# AltiumSTM32_Schematic.net
KiCad netlist of a schematic drawn in Altium Designer
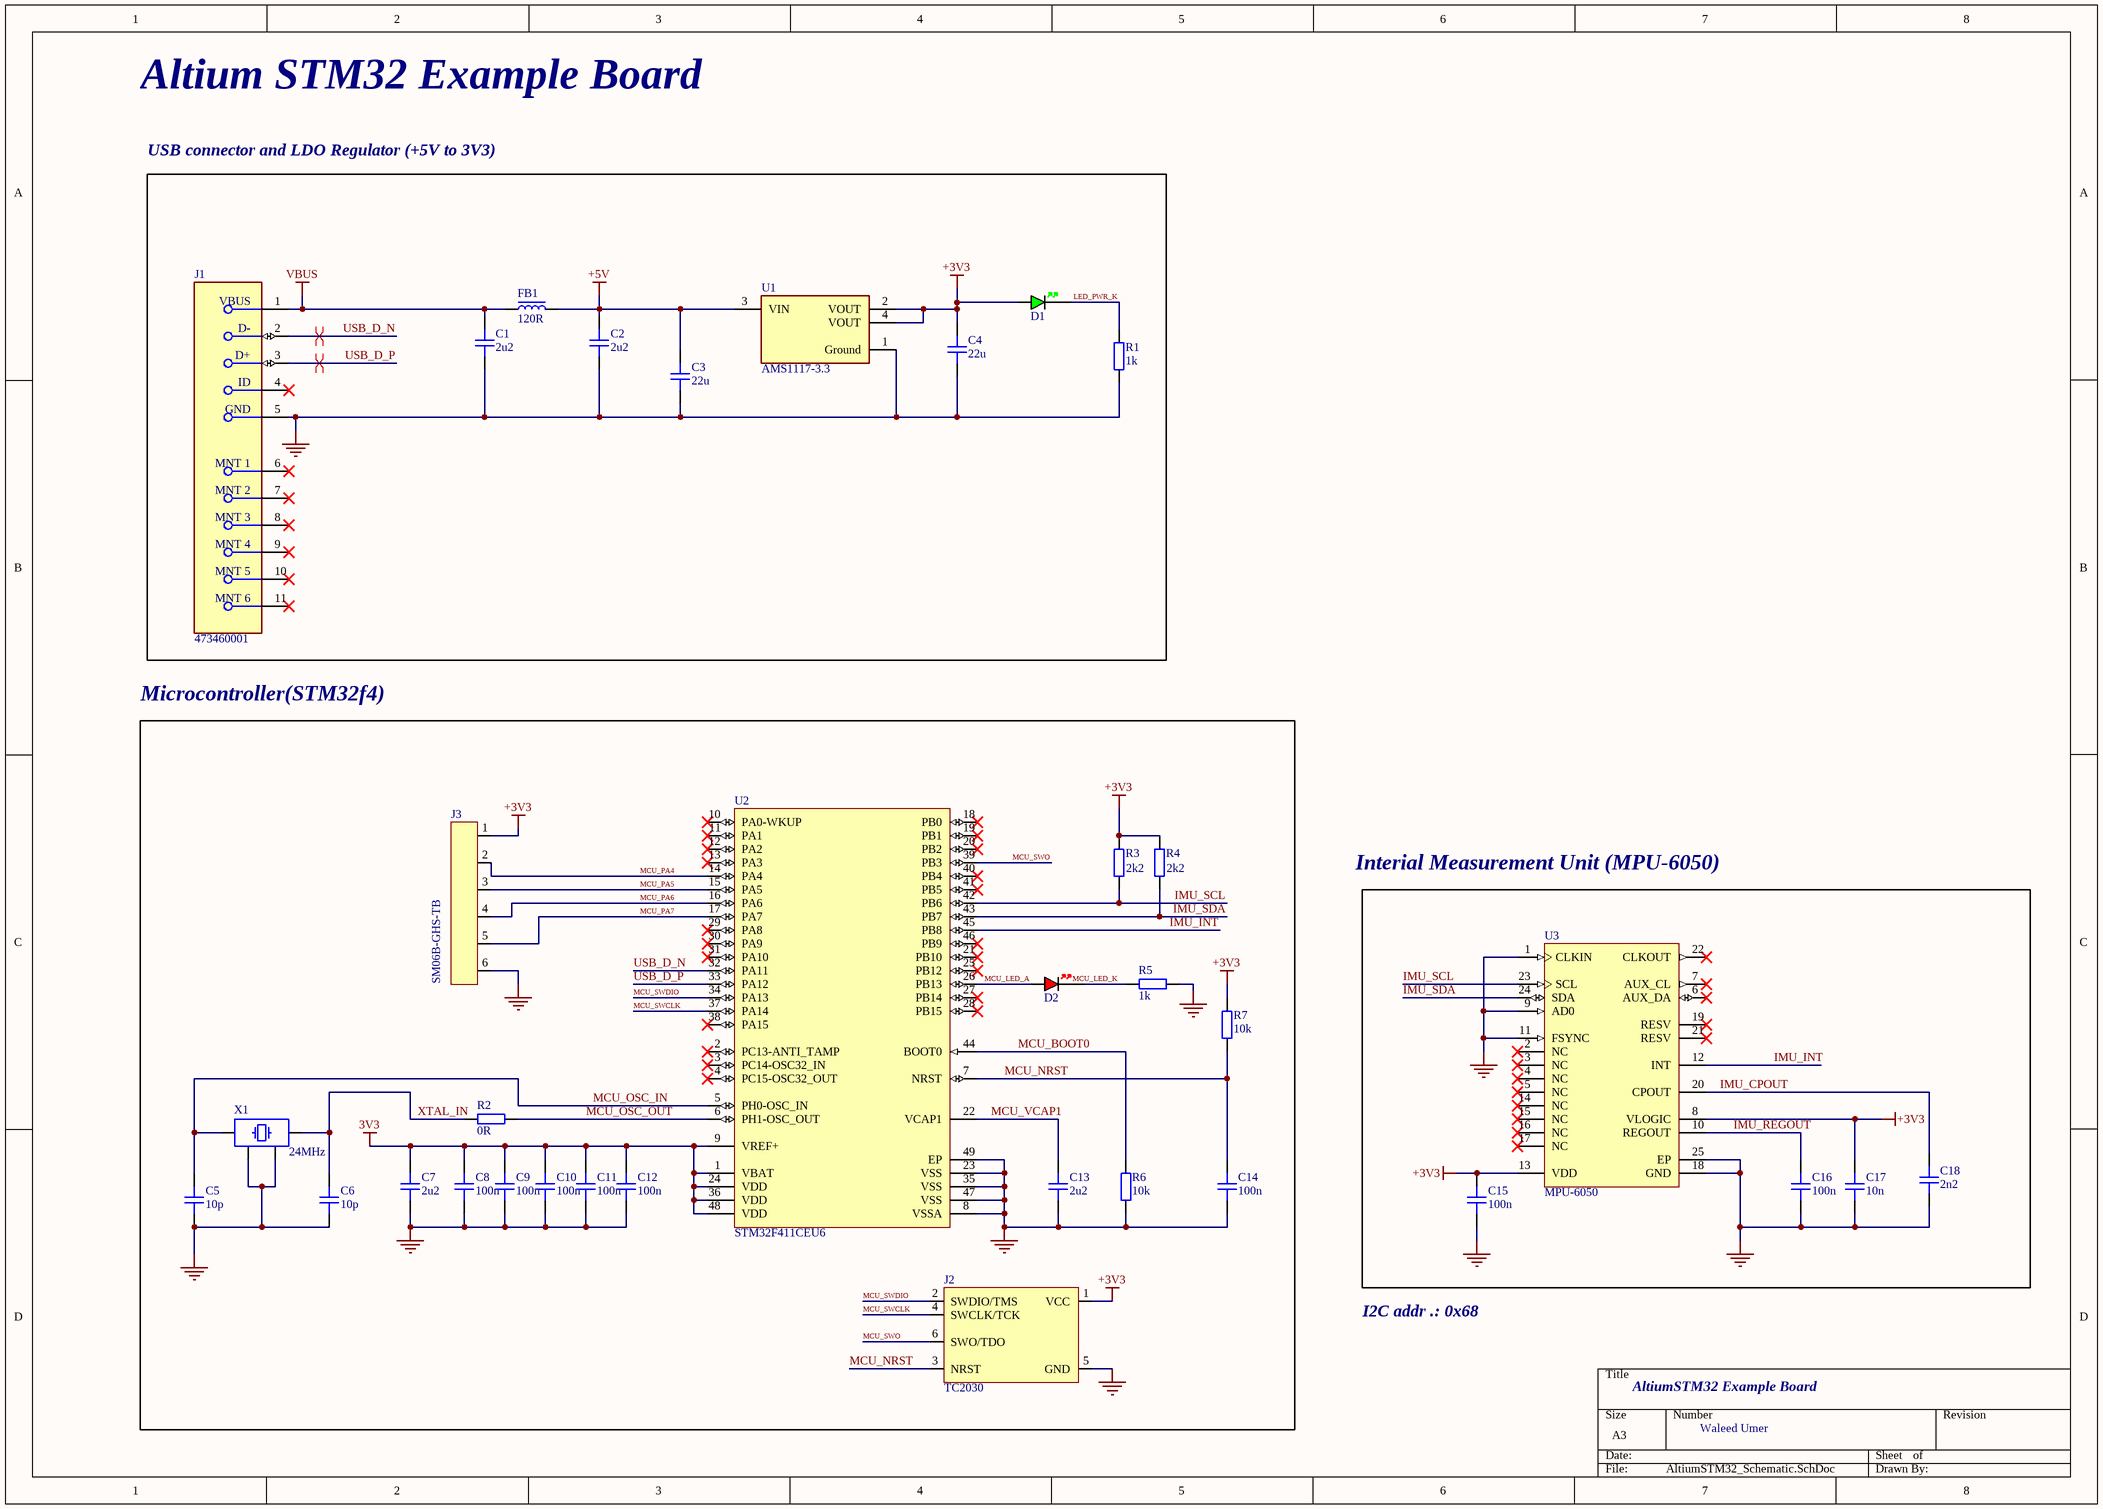
[diagram p0: AltiumSTM32_Schematic.SchDoc]

(export (version "E")
  (design (tool "Eeschema 10.0.6"))
  (components
    (comp (ref "C1")
      (value "2u2")
      (footprint "CAP_0603")
      (description "Capacitor SMD 0603")
      (libsource (lib "Schematic-Lib-PhilsLab") (part "CAP_0603"))
    )
    (comp (ref "C2")
      (value "2u2")
      (footprint "CAP_0603")
      (description "Capacitor SMD 0603")
      (libsource (lib "Schematic-Lib-PhilsLab") (part "CAP_0603"))
    )
    (comp (ref "C3")
      (value "22u")
      (footprint "CAP_0805")
      (description "Capacitor SMD 0805")
      (libsource (lib "Schematic-Lib-PhilsLab") (part "CAP_0805"))
    )
    (comp (ref "C4")
      (value "22u")
      (footprint "CAP_0805")
      (description "Capacitor SMD 0805")
      (libsource (lib "Schematic-Lib-PhilsLab") (part "CAP_0805"))
    )
    (comp (ref "C5")
      (value "10p")
      (footprint "CAP_0402")
      (description "Capacitor SMD 0402")
      (libsource (lib "Schematic-Lib-PhilsLab") (part "CAP_0402"))
    )
    (comp (ref "C6")
      (value "10p")
      (footprint "CAP_0402")
      (description "Capacitor SMD 0402")
      (libsource (lib "Schematic-Lib-PhilsLab") (part "CAP_0402"))
    )
    (comp (ref "C7")
      (value "2u2")
      (footprint "CAP_0603")
      (description "Capacitor SMD 0603")
      (libsource (lib "Schematic-Lib-PhilsLab") (part "CAP_0603"))
    )
    (comp (ref "C8")
      (value "100n")
      (footprint "CAP_0402")
      (description "Capacitor SMD 0402")
      (libsource (lib "Schematic-Lib-PhilsLab") (part "CAP_0402"))
    )
    (comp (ref "C9")
      (value "100n")
      (footprint "CAP_0402")
      (description "Capacitor SMD 0402")
      (libsource (lib "Schematic-Lib-PhilsLab") (part "CAP_0402"))
    )
    (comp (ref "C10")
      (value "100n")
      (footprint "CAP_0402")
      (description "Capacitor SMD 0402")
      (libsource (lib "Schematic-Lib-PhilsLab") (part "CAP_0402"))
    )
    (comp (ref "C11")
      (value "100n")
      (footprint "CAP_0402")
      (description "Capacitor SMD 0402")
      (libsource (lib "Schematic-Lib-PhilsLab") (part "CAP_0402"))
    )
    (comp (ref "C12")
      (value "100n")
      (footprint "CAP_0402")
      (description "Capacitor SMD 0402")
      (libsource (lib "Schematic-Lib-PhilsLab") (part "CAP_0402"))
    )
    (comp (ref "C13")
      (value "2u2")
      (footprint "CAP_0603")
      (description "Capacitor SMD 0603")
      (libsource (lib "Schematic-Lib-PhilsLab") (part "CAP_0603"))
    )
    (comp (ref "C14")
      (value "100n")
      (footprint "CAP_0402")
      (description "Capacitor SMD 0402")
      (libsource (lib "Schematic-Lib-PhilsLab") (part "CAP_0402"))
    )
    (comp (ref "C15")
      (value "100n")
      (footprint "CAP_0402")
      (description "Capacitor SMD 0402")
      (libsource (lib "Schematic-Lib-PhilsLab") (part "CAP_0402"))
    )
    (comp (ref "C16")
      (value "100n")
      (footprint "CAP_0402")
      (description "Capacitor SMD 0402")
      (libsource (lib "Schematic-Lib-PhilsLab") (part "CAP_0402"))
    )
    (comp (ref "C17")
      (value "10n")
      (footprint "CAP_0402")
      (description "Capacitor SMD 0402")
      (libsource (lib "Schematic-Lib-PhilsLab") (part "CAP_0402"))
    )
    (comp (ref "C18")
      (value "2n2")
      (footprint "CAP_0402")
      (description "Capacitor SMD 0402")
      (libsource (lib "Schematic-Lib-PhilsLab") (part "CAP_0402"))
    )
    (comp (ref "D1")
      (value "GREEN")
      (footprint "LED_0402_GREEN")
      (description "LED 0402 GREEN SMD")
      (libsource (lib "Schematic-Lib-PhilsLab") (part "LED_0402_GREEN"))
    )
    (comp (ref "D2")
      (value "RED")
      (footprint "LED_0402_RED")
      (description "LED 0402 RED SMD")
      (libsource (lib "Schematic-Lib-PhilsLab") (part "LED_0402_RED"))
    )
    (comp (ref "FB1")
      (value "120R")
      (footprint "FB_0603")
      (description "Ferrite Bead SMD 0603")
      (libsource (lib "Schematic-Lib-PhilsLab") (part "FB_0603"))
    )
    (comp (ref "J1")
      (value "473460001")
      (footprint "FP-473460001-MFG")
      (description "CONN RCPT USB2.0 MICRO B SMD R/A")
      (fields
        (field (name "OCTOPART") "https://octopart.com/47346-0001-molex-7164928")
        (field (name "MANUFACTURER") "Molex")
      )
      (libsource (lib "Altium Content Vault") (part "53ae1f1d9b557310b43ca686e5bb76a"))
    )
    (comp (ref "J2")
      (value "TC2030")
      (footprint "TC2030-FP")
      (description "Tag-Connect No-Solder SWD Debug Connector DO NOT PLACE")
      (fields (field (name "MANUFACTURER") "Tag-Connect"))
      (libsource (lib "Schematic-Lib-PhilsLab") (part "TC2030"))
    )
    (comp (ref "J3")
      (value "SM06B-GHS-TB")
      (footprint "SM06B-GHS-TB")
      (description "Header Connector 6 Position 1.25MM Pitch SMD Horizontal JST GH")
      (fields (field (name "MANUFACTURER") "JST"))
      (libsource (lib "Schematic-Lib-PhilsLab") (part "SM06B-GHS-TB"))
    )
    (comp (ref "R1")
      (value "1k")
      (footprint "RES_0402")
      (description "Resistor SMD 0402")
      (libsource (lib "Schematic-Lib-PhilsLab") (part "RES_0402"))
    )
    (comp (ref "R2")
      (value "0R")
      (footprint "RES_0402")
      (description "Resistor SMD 0402")
      (libsource (lib "Schematic-Lib-PhilsLab") (part "RES_0402"))
    )
    (comp (ref "R3")
      (value "2k2")
      (footprint "RES_0402")
      (description "Resistor SMD 0402")
      (libsource (lib "Schematic-Lib-PhilsLab") (part "RES_0402"))
    )
    (comp (ref "R4")
      (value "2k2")
      (footprint "RES_0402")
      (description "Resistor SMD 0402")
      (libsource (lib "Schematic-Lib-PhilsLab") (part "RES_0402"))
    )
    (comp (ref "R5")
      (value "1k")
      (footprint "RES_0402")
      (description "Resistor SMD 0402")
      (libsource (lib "Schematic-Lib-PhilsLab") (part "RES_0402"))
    )
    (comp (ref "R6")
      (value "10k")
      (footprint "RES_0402")
      (description "Resistor SMD 0402")
      (libsource (lib "Schematic-Lib-PhilsLab") (part "RES_0402"))
    )
    (comp (ref "R7")
      (value "10k")
      (footprint "RES_0402")
      (description "Resistor SMD 0402")
      (libsource (lib "Schematic-Lib-PhilsLab") (part "RES_0402"))
    )
    (comp (ref "U1")
      (value "AMS1117-3.3")
      (footprint "FP-AMS1117-IPC_C")
      (description "LDO Voltage Regulators 1A, 3.3V")
      (fields
        (field (name "OCTOPART") "https://octopart.com/ams1117-3.3-advanced+monolithic+systems-25899300")
        (field (name "MANUFACTURER") "Advanced Monolithic Systems")
      )
      (libsource (lib "Altium Content Vault") (part "8bdbb5f8e77002000e30dd2845d0354"))
    )
    (comp (ref "U2")
      (value "STM32F411CEU6")
      (footprint "STM-UFQFPN48_L")
      (libsource (lib "Altium Content Vault") (part "MC-ARM-STM32F411-UFQFPN48"))
    )
    (comp (ref "U3")
      (value "MPU-6050")
      (footprint "IS-QFN-24_V")
      (fields (field (name "MANUFACTURER") "InvenSense"))
      (libsource (lib "Altium Content Vault") (part "IS-MPU-6050-QFN-24"))
    )
    (comp (ref "X1")
      (value "24MHz")
      (footprint "XTAL_3225")
      (description "Crystal SMD 24MHz 10PPM 7pF 3225")
      (fields
        (field (name "MANUFACTURER") "Epson")
        (field (name "MANUFACTURER PART NUMBER") "TSX-3225 24.0000MF15X-AC")
      )
      (libsource (lib "Schematic-Lib-PhilsLab") (part "TSX-3225_24.0000MF15X-AC"))
    )
  )
  (nets
    (net (code "1") (name "+3V3") (class "Default")
      (node (ref "C15") (pin "2") (pinfunction "2_2") (pintype "passive"))
      (node (ref "C17") (pin "2") (pinfunction "2_2") (pintype "passive"))
      (node (ref "C4") (pin "2") (pinfunction "2_2") (pintype "passive"))
      (node (ref "D1") (pin "A") (pinfunction "A_A") (pintype "passive"))
      (node (ref "J2") (pin "1") (pinfunction "VCC_1") (pintype "passive"))
      (node (ref "J3") (pin "1") (pinfunction "1_1") (pintype "passive"))
      (node (ref "R3") (pin "2") (pinfunction "2_2") (pintype "passive"))
      (node (ref "R4") (pin "2") (pinfunction "2_2") (pintype "passive"))
      (node (ref "R7") (pin "2") (pinfunction "2_2") (pintype "passive"))
      (node (ref "U1") (pin "2") (pinfunction "VOUT_2") (pintype "passive"))
      (node (ref "U1") (pin "4") (pinfunction "VOUT_4") (pintype "passive"))
      (node (ref "U3") (pin "13") (pinfunction "VDD_13") (pintype "power_in"))
      (node (ref "U3") (pin "8") (pinfunction "VLOGIC_8") (pintype "power_in"))
    )
    (net (code "2") (name "+5V") (class "Default")
      (node (ref "C2") (pin "2") (pinfunction "2_2") (pintype "passive"))
      (node (ref "C3") (pin "2") (pinfunction "2_2") (pintype "passive"))
      (node (ref "FB1") (pin "2") (pinfunction "2_2") (pintype "passive"))
      (node (ref "U1") (pin "3") (pinfunction "VIN_3") (pintype "power_in"))
    )
    (net (code "3") (name "/IMU_CPOUT") (class "Default")
      (node (ref "C18") (pin "1") (pinfunction "1_1") (pintype "passive"))
      (node (ref "U3") (pin "20") (pinfunction "CPOUT_20") (pintype "passive"))
    )
    (net (code "4") (name "/IMU_INT") (class "Default")
      (node (ref "U2") (pin "45") (pinfunction "PB8_45") (pintype "bidirectional"))
      (node (ref "U3") (pin "12") (pinfunction "INT_12") (pintype "open_collector"))
    )
    (net (code "5") (name "/IMU_REGOUT") (class "Default")
      (node (ref "C16") (pin "2") (pinfunction "2_2") (pintype "passive"))
      (node (ref "U3") (pin "10") (pinfunction "REGOUT_10") (pintype "passive"))
    )
    (net (code "6") (name "/IMU_SCL") (class "Default")
      (node (ref "R3") (pin "1") (pinfunction "1_1") (pintype "passive"))
      (node (ref "U2") (pin "42") (pinfunction "PB6_42") (pintype "bidirectional"))
      (node (ref "U3") (pin "23") (pinfunction "SCL_23") (pintype "input"))
    )
    (net (code "7") (name "/IMU_SDA") (class "Default")
      (node (ref "R4") (pin "1") (pinfunction "1_1") (pintype "passive"))
      (node (ref "U2") (pin "43") (pinfunction "PB7_43") (pintype "bidirectional"))
      (node (ref "U3") (pin "24") (pinfunction "SDA_24") (pintype "bidirectional"))
    )
    (net (code "8") (name "/LED_PWR_K") (class "Default")
      (node (ref "D1") (pin "K") (pinfunction "K_K") (pintype "passive"))
      (node (ref "R1") (pin "2") (pinfunction "2_2") (pintype "passive"))
    )
    (net (code "9") (name "/MCU_BOOT0") (class "Default")
      (node (ref "R6") (pin "2") (pinfunction "2_2") (pintype "passive"))
      (node (ref "U2") (pin "44") (pinfunction "BOOT0_44") (pintype "input"))
    )
    (net (code "10") (name "/MCU_LED_A") (class "Default")
      (node (ref "D2") (pin "A") (pinfunction "A_A") (pintype "passive"))
      (node (ref "U2") (pin "26") (pinfunction "PB13_26") (pintype "bidirectional"))
    )
    (net (code "11") (name "/MCU_LED_K") (class "Default")
      (node (ref "D2") (pin "K") (pinfunction "K_K") (pintype "passive"))
      (node (ref "R5") (pin "2") (pinfunction "2_2") (pintype "passive"))
    )
    (net (code "12") (name "/MCU_NRST") (class "Default")
      (node (ref "C14") (pin "2") (pinfunction "2_2") (pintype "passive"))
      (node (ref "J2") (pin "3") (pinfunction "NRST_3") (pintype "passive"))
      (node (ref "R7") (pin "1") (pinfunction "1_1") (pintype "passive"))
      (node (ref "U2") (pin "7") (pinfunction "NRST_7") (pintype "bidirectional"))
    )
    (net (code "13") (name "/MCU_OSC_IN") (class "Default")
      (node (ref "C5") (pin "2") (pinfunction "2_2") (pintype "passive"))
      (node (ref "U2") (pin "5") (pinfunction "PH0-OSC_IN_5") (pintype "bidirectional"))
      (node (ref "X1") (pin "1") (pinfunction "1_1") (pintype "passive"))
    )
    (net (code "14") (name "/MCU_OSC_OUT") (class "Default")
      (node (ref "R2") (pin "2") (pinfunction "2_2") (pintype "passive"))
      (node (ref "U2") (pin "6") (pinfunction "PH1-OSC_OUT_6") (pintype "bidirectional"))
    )
    (net (code "15") (name "/MCU_PA4") (class "Default")
      (node (ref "J3") (pin "2") (pinfunction "2_2") (pintype "passive"))
      (node (ref "U2") (pin "14") (pinfunction "PA4_14") (pintype "bidirectional"))
    )
    (net (code "16") (name "/MCU_PA5") (class "Default")
      (node (ref "J3") (pin "3") (pinfunction "3_3") (pintype "passive"))
      (node (ref "U2") (pin "15") (pinfunction "PA5_15") (pintype "bidirectional"))
    )
    (net (code "17") (name "/MCU_PA6") (class "Default")
      (node (ref "J3") (pin "4") (pinfunction "4_4") (pintype "passive"))
      (node (ref "U2") (pin "16") (pinfunction "PA6_16") (pintype "bidirectional"))
    )
    (net (code "18") (name "/MCU_PA7") (class "Default")
      (node (ref "J3") (pin "5") (pinfunction "5_5") (pintype "passive"))
      (node (ref "U2") (pin "17") (pinfunction "PA7_17") (pintype "bidirectional"))
    )
    (net (code "19") (name "/MCU_SWCLK") (class "Default")
      (node (ref "J2") (pin "4") (pinfunction "SWCLK/TCK_4") (pintype "passive"))
      (node (ref "U2") (pin "37") (pinfunction "PA14_37") (pintype "bidirectional"))
    )
    (net (code "20") (name "/MCU_SWDIO") (class "Default")
      (node (ref "J2") (pin "2") (pinfunction "SWDIO/TMS_2") (pintype "passive"))
      (node (ref "U2") (pin "34") (pinfunction "PA13_34") (pintype "bidirectional"))
    )
    (net (code "21") (name "/MCU_SWO") (class "Default")
      (node (ref "J2") (pin "6") (pinfunction "SWO/TDO_6") (pintype "passive"))
      (node (ref "U2") (pin "39") (pinfunction "PB3_39") (pintype "bidirectional"))
    )
    (net (code "22") (name "/MCU_VCAP1") (class "Default")
      (node (ref "C13") (pin "2") (pinfunction "2_2") (pintype "passive"))
      (node (ref "U2") (pin "22") (pinfunction "VCAP1_22") (pintype "passive"))
    )
    (net (code "23") (name "/USB_D_N") (class "Default")
      (node (ref "J1") (pin "2") (pinfunction "D-_2") (pintype "bidirectional"))
      (node (ref "U2") (pin "32") (pinfunction "PA11_32") (pintype "bidirectional"))
    )
    (net (code "24") (name "/USB_D_P") (class "Default")
      (node (ref "J1") (pin "3") (pinfunction "D+_3") (pintype "bidirectional"))
      (node (ref "U2") (pin "33") (pinfunction "PA12_33") (pintype "bidirectional"))
    )
    (net (code "25") (name "/XTAL_IN") (class "Default")
      (node (ref "C6") (pin "2") (pinfunction "2_2") (pintype "passive"))
      (node (ref "R2") (pin "1") (pinfunction "1_1") (pintype "passive"))
      (node (ref "X1") (pin "3") (pinfunction "3_3") (pintype "passive"))
    )
    (net (code "26") (name "3V3") (class "Default")
      (node (ref "C10") (pin "2") (pinfunction "2_2") (pintype "passive"))
      (node (ref "C11") (pin "2") (pinfunction "2_2") (pintype "passive"))
      (node (ref "C12") (pin "2") (pinfunction "2_2") (pintype "passive"))
      (node (ref "C7") (pin "2") (pinfunction "2_2") (pintype "passive"))
      (node (ref "C8") (pin "2") (pinfunction "2_2") (pintype "passive"))
      (node (ref "C9") (pin "2") (pinfunction "2_2") (pintype "passive"))
      (node (ref "U2") (pin "1") (pinfunction "VBAT_1") (pintype "power_in"))
      (node (ref "U2") (pin "24") (pinfunction "VDD_24") (pintype "power_in"))
      (node (ref "U2") (pin "36") (pinfunction "VDD_36") (pintype "power_in"))
      (node (ref "U2") (pin "48") (pinfunction "VDD_48") (pintype "power_in"))
      (node (ref "U2") (pin "9") (pinfunction "VREF+_9") (pintype "power_in"))
    )
    (net (code "27") (name "GND") (class "Default")
      (node (ref "C1") (pin "1") (pinfunction "1_1") (pintype "passive"))
      (node (ref "C10") (pin "1") (pinfunction "1_1") (pintype "passive"))
      (node (ref "C11") (pin "1") (pinfunction "1_1") (pintype "passive"))
      (node (ref "C12") (pin "1") (pinfunction "1_1") (pintype "passive"))
      (node (ref "C13") (pin "1") (pinfunction "1_1") (pintype "passive"))
      (node (ref "C14") (pin "1") (pinfunction "1_1") (pintype "passive"))
      (node (ref "C15") (pin "1") (pinfunction "1_1") (pintype "passive"))
      (node (ref "C16") (pin "1") (pinfunction "1_1") (pintype "passive"))
      (node (ref "C17") (pin "1") (pinfunction "1_1") (pintype "passive"))
      (node (ref "C18") (pin "2") (pinfunction "2_2") (pintype "passive"))
      (node (ref "C2") (pin "1") (pinfunction "1_1") (pintype "passive"))
      (node (ref "C3") (pin "1") (pinfunction "1_1") (pintype "passive"))
      (node (ref "C4") (pin "1") (pinfunction "1_1") (pintype "passive"))
      (node (ref "C5") (pin "1") (pinfunction "1_1") (pintype "passive"))
      (node (ref "C6") (pin "1") (pinfunction "1_1") (pintype "passive"))
      (node (ref "C7") (pin "1") (pinfunction "1_1") (pintype "passive"))
      (node (ref "C8") (pin "1") (pinfunction "1_1") (pintype "passive"))
      (node (ref "C9") (pin "1") (pinfunction "1_1") (pintype "passive"))
      (node (ref "J1") (pin "5") (pinfunction "GND_5") (pintype "power_in"))
      (node (ref "J2") (pin "5") (pinfunction "GND_5") (pintype "passive"))
      (node (ref "J3") (pin "6") (pinfunction "6_6") (pintype "passive"))
      (node (ref "R1") (pin "1") (pinfunction "1_1") (pintype "passive"))
      (node (ref "R5") (pin "1") (pinfunction "1_1") (pintype "passive"))
      (node (ref "R6") (pin "1") (pinfunction "1_1") (pintype "passive"))
      (node (ref "U1") (pin "1") (pinfunction "Ground_1") (pintype "power_in"))
      (node (ref "U2") (pin "23") (pinfunction "VSS_23") (pintype "power_in"))
      (node (ref "U2") (pin "35") (pinfunction "VSS_35") (pintype "power_in"))
      (node (ref "U2") (pin "47") (pinfunction "VSS_47") (pintype "power_in"))
      (node (ref "U2") (pin "49") (pinfunction "EP_49") (pintype "power_in"))
      (node (ref "U2") (pin "8") (pinfunction "VSSA_8") (pintype "power_in"))
      (node (ref "U3") (pin "1") (pinfunction "CLKIN_1") (pintype "input"))
      (node (ref "U3") (pin "11") (pinfunction "FSYNC_11") (pintype "input"))
      (node (ref "U3") (pin "18") (pinfunction "GND_18") (pintype "power_in"))
      (node (ref "U3") (pin "25") (pinfunction "EP_25") (pintype "power_in"))
      (node (ref "U3") (pin "9") (pinfunction "AD0_9") (pintype "input"))
      (node (ref "X1") (pin "2") (pinfunction "2_2") (pintype "passive"))
      (node (ref "X1") (pin "4") (pinfunction "4_4") (pintype "passive"))
    )
    (net (code "28") (name "VBUS") (class "Default")
      (node (ref "C1") (pin "2") (pinfunction "2_2") (pintype "passive"))
      (node (ref "FB1") (pin "1") (pinfunction "1_1") (pintype "passive"))
      (node (ref "J1") (pin "1") (pinfunction "VBUS_1") (pintype "power_in"))
    )
    (net (code "29") (name "unconnected-(J1-ID-Pad4)") (class "Default")
      (node (ref "J1") (pin "4") (pinfunction "ID_4") (pintype "passive+no_connect"))
    )
    (net (code "30") (name "unconnected-(J1-MNT_1-Pad6)") (class "Default")
      (node (ref "J1") (pin "6") (pinfunction "MNT_1_6") (pintype "passive+no_connect"))
    )
    (net (code "31") (name "unconnected-(J1-MNT_2-Pad7)") (class "Default")
      (node (ref "J1") (pin "7") (pinfunction "MNT_2_7") (pintype "passive+no_connect"))
    )
    (net (code "32") (name "unconnected-(J1-MNT_3-Pad8)") (class "Default")
      (node (ref "J1") (pin "8") (pinfunction "MNT_3_8") (pintype "passive+no_connect"))
    )
    (net (code "33") (name "unconnected-(J1-MNT_4-Pad9)") (class "Default")
      (node (ref "J1") (pin "9") (pinfunction "MNT_4_9") (pintype "passive+no_connect"))
    )
    (net (code "34") (name "unconnected-(J1-MNT_5-Pad10)") (class "Default")
      (node (ref "J1") (pin "10") (pinfunction "MNT_5_10") (pintype "passive+no_connect"))
    )
    (net (code "35") (name "unconnected-(J1-MNT_6-Pad11)") (class "Default")
      (node (ref "J1") (pin "11") (pinfunction "MNT_6_11") (pintype "passive+no_connect"))
    )
    (net (code "36") (name "unconnected-(U2-PA0-WKUP-Pad10)") (class "Default")
      (node (ref "U2") (pin "10") (pinfunction "PA0-WKUP_10") (pintype "bidirectional+no_connect"))
    )
    (net (code "37") (name "unconnected-(U2-PA1-Pad11)") (class "Default")
      (node (ref "U2") (pin "11") (pinfunction "PA1_11") (pintype "bidirectional+no_connect"))
    )
    (net (code "38") (name "unconnected-(U2-PA2-Pad12)") (class "Default")
      (node (ref "U2") (pin "12") (pinfunction "PA2_12") (pintype "bidirectional+no_connect"))
    )
    (net (code "39") (name "unconnected-(U2-PA3-Pad13)") (class "Default")
      (node (ref "U2") (pin "13") (pinfunction "PA3_13") (pintype "bidirectional+no_connect"))
    )
    (net (code "40") (name "unconnected-(U2-PA8-Pad29)") (class "Default")
      (node (ref "U2") (pin "29") (pinfunction "PA8_29") (pintype "bidirectional+no_connect"))
    )
    (net (code "41") (name "unconnected-(U2-PA9-Pad30)") (class "Default")
      (node (ref "U2") (pin "30") (pinfunction "PA9_30") (pintype "bidirectional+no_connect"))
    )
    (net (code "42") (name "unconnected-(U2-PA10-Pad31)") (class "Default")
      (node (ref "U2") (pin "31") (pinfunction "PA10_31") (pintype "bidirectional+no_connect"))
    )
    (net (code "43") (name "unconnected-(U2-PA15-Pad38)") (class "Default")
      (node (ref "U2") (pin "38") (pinfunction "PA15_38") (pintype "bidirectional+no_connect"))
    )
    (net (code "44") (name "unconnected-(U2-PB0-Pad18)") (class "Default")
      (node (ref "U2") (pin "18") (pinfunction "PB0_18") (pintype "bidirectional+no_connect"))
    )
    (net (code "45") (name "unconnected-(U2-PB1-Pad19)") (class "Default")
      (node (ref "U2") (pin "19") (pinfunction "PB1_19") (pintype "bidirectional+no_connect"))
    )
    (net (code "46") (name "unconnected-(U2-PB2-Pad20)") (class "Default")
      (node (ref "U2") (pin "20") (pinfunction "PB2_20") (pintype "bidirectional+no_connect"))
    )
    (net (code "47") (name "unconnected-(U2-PB4-Pad40)") (class "Default")
      (node (ref "U2") (pin "40") (pinfunction "PB4_40") (pintype "bidirectional+no_connect"))
    )
    (net (code "48") (name "unconnected-(U2-PB5-Pad41)") (class "Default")
      (node (ref "U2") (pin "41") (pinfunction "PB5_41") (pintype "bidirectional+no_connect"))
    )
    (net (code "49") (name "unconnected-(U2-PB9-Pad46)") (class "Default")
      (node (ref "U2") (pin "46") (pinfunction "PB9_46") (pintype "bidirectional+no_connect"))
    )
    (net (code "50") (name "unconnected-(U2-PB10-Pad21)") (class "Default")
      (node (ref "U2") (pin "21") (pinfunction "PB10_21") (pintype "bidirectional+no_connect"))
    )
    (net (code "51") (name "unconnected-(U2-PB12-Pad25)") (class "Default")
      (node (ref "U2") (pin "25") (pinfunction "PB12_25") (pintype "bidirectional+no_connect"))
    )
    (net (code "52") (name "unconnected-(U2-PB14-Pad27)") (class "Default")
      (node (ref "U2") (pin "27") (pinfunction "PB14_27") (pintype "bidirectional+no_connect"))
    )
    (net (code "53") (name "unconnected-(U2-PB15-Pad28)") (class "Default")
      (node (ref "U2") (pin "28") (pinfunction "PB15_28") (pintype "bidirectional+no_connect"))
    )
    (net (code "54") (name "unconnected-(U2-PC13-ANTI_TAMP-Pad2)") (class "Default")
      (node (ref "U2") (pin "2") (pinfunction "PC13-ANTI_TAMP_2") (pintype "bidirectional+no_connect"))
    )
    (net (code "55") (name "unconnected-(U2-PC14-OSC32_IN-Pad3)") (class "Default")
      (node (ref "U2") (pin "3") (pinfunction "PC14-OSC32_IN_3") (pintype "bidirectional+no_connect"))
    )
    (net (code "56") (name "unconnected-(U2-PC15-OSC32_OUT-Pad4)") (class "Default")
      (node (ref "U2") (pin "4") (pinfunction "PC15-OSC32_OUT_4") (pintype "bidirectional+no_connect"))
    )
    (net (code "57") (name "unconnected-(U3-AUX_CL-Pad7)") (class "Default")
      (node (ref "U3") (pin "7") (pinfunction "AUX_CL_7") (pintype "output+no_connect"))
    )
    (net (code "58") (name "unconnected-(U3-AUX_DA-Pad6)") (class "Default")
      (node (ref "U3") (pin "6") (pinfunction "AUX_DA_6") (pintype "bidirectional+no_connect"))
    )
    (net (code "59") (name "unconnected-(U3-CLKOUT-Pad22)") (class "Default")
      (node (ref "U3") (pin "22") (pinfunction "CLKOUT_22") (pintype "output+no_connect"))
    )
    (net (code "60") (name "unconnected-(U3-NC-Pad2)") (class "Default")
      (node (ref "U3") (pin "2") (pinfunction "NC_2") (pintype "passive+no_connect"))
    )
    (net (code "61") (name "unconnected-(U3-NC-Pad3)") (class "Default")
      (node (ref "U3") (pin "3") (pinfunction "NC_3") (pintype "passive+no_connect"))
    )
    (net (code "62") (name "unconnected-(U3-NC-Pad4)") (class "Default")
      (node (ref "U3") (pin "4") (pinfunction "NC_4") (pintype "passive+no_connect"))
    )
    (net (code "63") (name "unconnected-(U3-NC-Pad5)") (class "Default")
      (node (ref "U3") (pin "5") (pinfunction "NC_5") (pintype "passive+no_connect"))
    )
    (net (code "64") (name "unconnected-(U3-NC-Pad14)") (class "Default")
      (node (ref "U3") (pin "14") (pinfunction "NC_14") (pintype "passive+no_connect"))
    )
    (net (code "65") (name "unconnected-(U3-NC-Pad15)") (class "Default")
      (node (ref "U3") (pin "15") (pinfunction "NC_15") (pintype "passive+no_connect"))
    )
    (net (code "66") (name "unconnected-(U3-NC-Pad16)") (class "Default")
      (node (ref "U3") (pin "16") (pinfunction "NC_16") (pintype "passive+no_connect"))
    )
    (net (code "67") (name "unconnected-(U3-NC-Pad17)") (class "Default")
      (node (ref "U3") (pin "17") (pinfunction "NC_17") (pintype "passive+no_connect"))
    )
    (net (code "68") (name "unconnected-(U3-RESV-Pad19)") (class "Default")
      (node (ref "U3") (pin "19") (pinfunction "RESV_19") (pintype "passive+no_connect"))
    )
    (net (code "69") (name "unconnected-(U3-RESV-Pad21)") (class "Default")
      (node (ref "U3") (pin "21") (pinfunction "RESV_21") (pintype "passive+no_connect"))
    )
  )
)
